# SKEMA_GAMBAR_TEKNIK.net
KiCad netlist of a schematic drawn in EAGLE
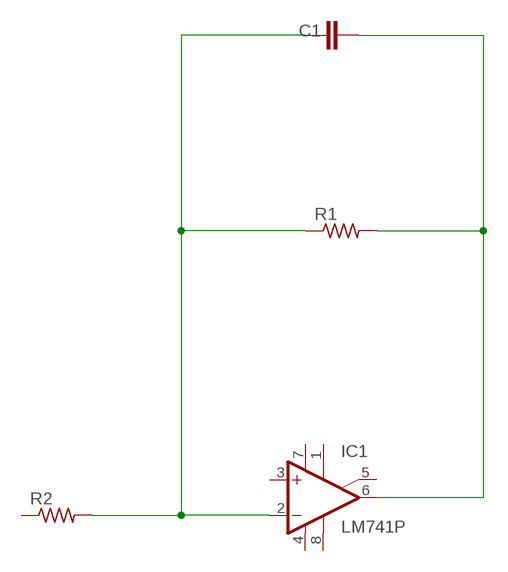
[diagram p0: schematic, sheet 1]

(export (version "E")
  (design (tool "Eeschema 10.0.6"))
  (components
    (comp (ref "C1")
      (value "C-EUC0603")
      (footprint "eagle-import:C0603")
      (libsource (lib "eagle-import") (part "C-EUC0603"))
    )
    (comp (ref "IC1")
      (value "LM741P")
      (footprint "eagle-import:DIL08")
      (libsource (lib "eagle-import") (part "741PLM"))
    )
    (comp (ref "R1")
      (value "R-US_R0603")
      (footprint "eagle-import:R0603")
      (libsource (lib "eagle-import") (part "R-US_R0603"))
    )
    (comp (ref "R2")
      (value "R-US_R0603")
      (footprint "eagle-import:R0603")
      (libsource (lib "eagle-import") (part "R-US_R0603"))
    )
  )
  (nets
    (net (code "1") (name "/V+") (class "Default")
      (node (ref "IC1") (pin "7") (pinfunction "V+_7") (pintype "power_in"))
    )
    (net (code "2") (name "/V-") (class "Default")
      (node (ref "IC1") (pin "4") (pinfunction "V-_4") (pintype "power_in"))
    )
    (net (code "3") (name "Net-(IC1--IN)") (class "Default")
      (node (ref "C1") (pin "1") (pinfunction "1_1") (pintype "passive"))
      (node (ref "IC1") (pin "2") (pinfunction "-IN_2") (pintype "input"))
      (node (ref "R1") (pin "1") (pinfunction "1_1") (pintype "passive"))
      (node (ref "R2") (pin "2") (pinfunction "2_2") (pintype "passive"))
    )
    (net (code "4") (name "Net-(IC1-OUT)") (class "Default")
      (node (ref "C1") (pin "2") (pinfunction "2_2") (pintype "passive"))
      (node (ref "IC1") (pin "6") (pinfunction "OUT_6") (pintype "output"))
      (node (ref "R1") (pin "2") (pinfunction "2_2") (pintype "passive"))
    )
    (net (code "5") (name "unconnected-(IC1-+IN-Pad3)") (class "Default")
      (node (ref "IC1") (pin "3") (pinfunction "+IN_3") (pintype "input"))
    )
    (net (code "6") (name "unconnected-(IC1-ON1-Pad1)") (class "Default")
      (node (ref "IC1") (pin "1") (pinfunction "ON1_1") (pintype "passive"))
    )
    (net (code "7") (name "unconnected-(IC1-ON2-Pad5)") (class "Default")
      (node (ref "IC1") (pin "5") (pinfunction "ON2_5") (pintype "passive"))
    )
    (net (code "8") (name "unconnected-(IC1-OPT-Pad8)") (class "Default")
      (node (ref "IC1") (pin "8") (pinfunction "OPT_8") (pintype "passive"))
    )
    (net (code "9") (name "unconnected-(R2-Pad1)") (class "Default")
      (node (ref "R2") (pin "1") (pinfunction "1_1") (pintype "passive"))
    )
  )
)
